# Main.net
KiCad netlist of a schematic drawn in Altium Designer
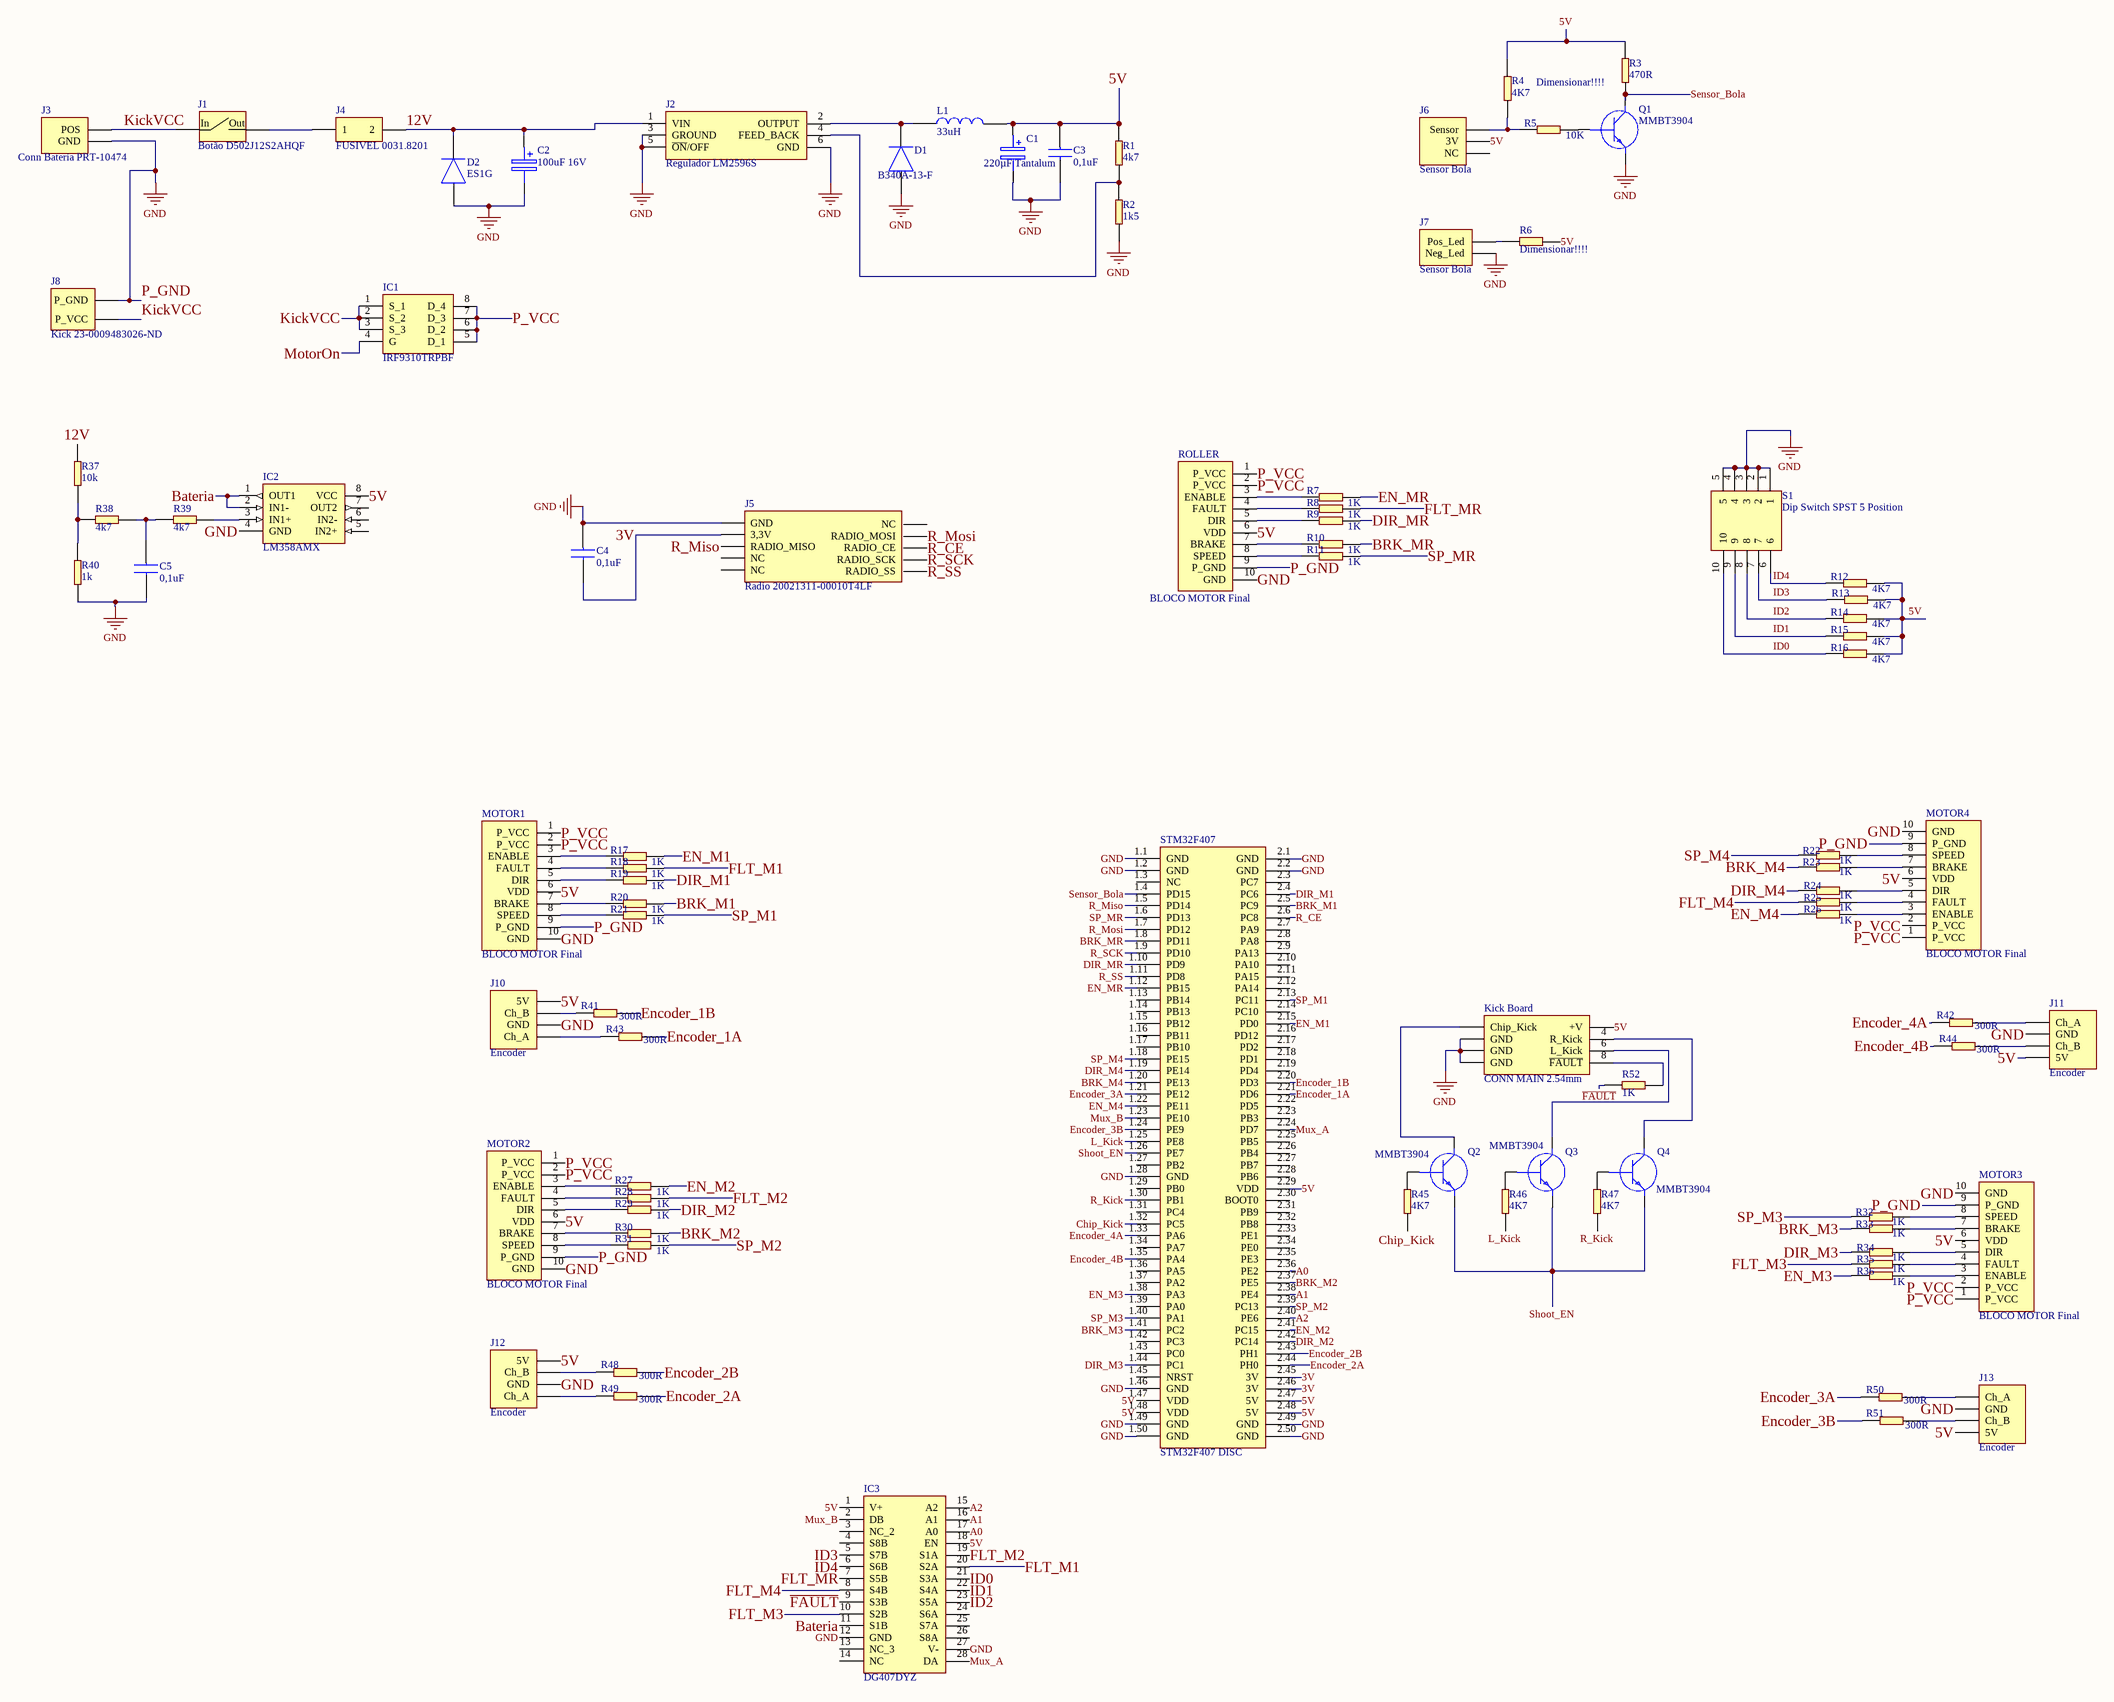
[diagram p0: Main.SchDoc]

(export (version "E")
  (design (tool "Eeschema 10.0.6"))
  (components
    (comp (ref "C1")
      (value "220µF Tantalum")
      (footprint "LIB_PCB_MAIN:CAP C2 SMD 6032 (2312)")
      (fields
        (field (name "MANUFACTURER_PART_NUMBER") "EEE-FK1E101P")
        (field (name "MOUSER PART NUMBER") "667-EEE-FK1E101P")
      )
      (libsource (lib "LIB_SCH_MAIN") (part "CAP C2 Tantalum"))
    )
    (comp (ref "C2")
      (value "100uF 16V")
      (footprint "LIB_PCB_MAIN:C1 CAP ALUM SMD")
      (fields
        (field (name "MANUFACTURER_PART_NUMBER") "EEE-1CA101WP")
        (field (name "MOUSER PART NUMBER") "667-EEE-1CA101WP")
        (field (name "RS PART NUMBER") "8077884")
      )
      (libsource (lib "LIB_SCH_MAIN") (part "C1 CAP ALUM 16V EEE-1CA101WP"))
    )
    (comp (ref "C3")
      (value "0,1uF")
      (footprint "LIB_PCB_MAIN:CAP C3 0603 SMD")
      (fields
        (field (name "MANUFACTURER_PART_NUMBER") "C3216C0G1H103J060AA")
        (field (name "MOUSER PART NUMBER") "810-C3216C0G1H103J-1")
        (field (name "RS PART NUMBER") "7407467P")
      )
      (libsource (lib "LIB_SCH_MAIN") (part "CAP C3 0603"))
    )
    (comp (ref "C4")
      (value "0,1uF")
      (footprint "LIB_PCB_MAIN:CAP C3 0603 SMD")
      (fields
        (field (name "MANUFACTURER_PART_NUMBER") "C3216C0G1H103J060AA")
        (field (name "MOUSER PART NUMBER") "810-C3216C0G1H103J-1")
        (field (name "RS PART NUMBER") "7407467P")
      )
      (libsource (lib "LIB_SCH_MAIN") (part "CAP C3 0603"))
    )
    (comp (ref "C5")
      (value "0,1uF")
      (footprint "LIB_PCB_MAIN:CAP C3 0603 SMD")
      (fields
        (field (name "MANUFACTURER_PART_NUMBER") "C3216C0G1H103J060AA")
        (field (name "MOUSER PART NUMBER") "810-C3216C0G1H103J-1")
        (field (name "RS PART NUMBER") "7407467P")
      )
      (libsource (lib "LIB_SCH_MAIN") (part "CAP C3 0603"))
    )
    (comp (ref "D1")
      (value "B340A-13-F")
      (footprint "LIB_PCB_MAIN:Diodo D1, D2")
      (description "Diode Schottky 40V 3A Surface Mount SMA\r\n\r\nB340A-FDITR-ND\r\n\r\nB340A-13-F")
      (fields (field (name "MANUFACTURER_PART_NUMBER") "ES1G"))
      (libsource (lib "LIB_SCH_MAIN") (part "Diodo D2 B340A-13-F"))
    )
    (comp (ref "D2")
      (value "ES1G")
      (footprint "LIB_PCB_MAIN:Diodo D1, D2")
      (description "Diode Standard 400V 1A Surface Mount SMA (DO-214AC)\r\n\r\nS1GFSCT-ND")
      (libsource (lib "LIB_SCH_MAIN") (part "Diodo D1 ES1G"))
    )
    (comp (ref "IC1")
      (value "IRF9310TRPBF")
      (footprint "LIB_PCB_MAIN:Mosfet P_VCC")
      (fields
        (field (name "MANUFACTURER_PART_NUMBER") "IRF9310PBF")
        (field (name "MOUSER PART NUMBER") "942-IRF9310PBF")
        (field (name "RS PART NUMBER") "7259234P")
      )
      (libsource (lib "LIB_SCH_MAIN") (part "Mosfet P_VCC"))
    )
    (comp (ref "IC2")
      (value "LM358AMX")
      (footprint "LIB_PCB_MAIN:OP AMP Bateria")
      (fields (field (name "MOUSER PART NUMBER") "512-LM358AMX") (field (name "RS PART NUMBER") "7599399P"))
      (libsource (lib "LIB_SCH_MAIN") (part "OP AMP Bateria"))
    )
    (comp (ref "IC3")
      (value "DG407DYZ")
      (footprint "LIB_PCB_MAIN:MUX 2x 8:1")
      (description "IC MULTIPLEXER DUAL 8X1 28SOIC\r\n\r\n2 Circuit IC Switch 8:1 100Ohm 28-SOIC\r\n\r\nDG407DYZ")
      (fields (field (name "MOUSER PART NUMBER") "968-DG407DYZ"))
      (libsource (lib "LIB_SCH_MAIN") (part "MUX 2x 8{colon}1"))
    )
    (comp (ref "J1")
      (value "Botão D502J12S2AHQF")
      (footprint "LIB_PCB_MAIN:Botão Bateria Main")
      (fields
        (field (name "MANUFACTURER_PART_NUMBER") "0031.8201")
        (field (name "MOUSER PART NUMBER") "693-0031.8201")
        (field (name "RS PART NUMBER") "2508764386")
      )
      (libsource (lib "LIB_SCH_MAIN") (part "Botão Bateria Main"))
    )
    (comp (ref "J2")
      (value "Regulador LM2596S")
      (footprint "LIB_PCB_MAIN:LM2596S50TR")
      (fields (field (name "MANUFACTURER_PART_NUMBER") "LM2596S-5.0/TR"))
      (libsource (lib "LIB_SCH_Main") (part "Regulador LM2596S 12V - 5V"))
    )
    (comp (ref "J3")
      (value "Conn Bateria PRT-10474")
      (footprint "LIB_PCB_MAIN:Conn Bateria Bolado")
      (description "XT60 CONNECTORS MALE\r\n\r\nPRT-10474\r\n\r\n1568-1816-ND")
      (fields
        (field (name "MANUFACTURER_PART_NUMBER") "PRT-10474")
        (field (name "MOUSER PART NUMBER") "474-PRT-10474")
      )
      (libsource (lib "LIB_SCH_MAIN") (part "Conn Bateria Bolado"))
    )
    (comp (ref "J4")
      (value "FUSIVEL 0031.8201")
      (footprint "LIB_PCB_MAIN:PORTA FUSIVEL")
      (description "Fuse Block 10A 500V 1 Circuit Cartridge Through Hole\r\n\r\n486-1258-ND\r\n\r\n0031.8201")
      (fields
        (field (name "MANUFACTURER_PART_NUMBER") "0031.8201")
        (field (name "MOUSER PART NUMBER") "693-0031.8201")
      )
      (libsource (lib "LIB_SCH_MAIN") (part "PORTA FUSIVEL 0031.8201"))
    )
    (comp (ref "J5")
      (value "Radio 20021311-00010T4LF")
      (footprint "LIB_PCB_MAIN:CONN Radio")
      (description "CONN RCPT 1.27mm 10POS 0.05 GOLD PCB\r\n\r\n20021311-00010T4LF\r\n\r\n609-3754-ND")
      (fields
        (field (name "MANUFACTURER_PART_NUMBER") "20021311-00010T4LF")
        (field (name "MOUSER PART NUMBER") "649-221311-00010T4LF")
      )
      (libsource (lib "LIB_SCH_Main") (part "CONN RADIO"))
    )
    (comp (ref "J6")
      (value "Sensor Bola")
      (footprint "LIB_PCB_MAIN:Conn Receptor Infra")
      (fields
        (field (name "MANUFACTURER_PART_NUMBER") "292161-3")
        (field (name "MOUSER PART NUMBER") "571-292161-3")
        (field (name "RS PART NUMBER") "6801610")
      )
      (libsource (lib "LIB_SCH_MAIN") (part "Conn Receptor Infra"))
    )
    (comp (ref "J7")
      (value "Sensor Bola")
      (footprint "LIB_PCB_MAIN:Conn Emisor Infra")
      (fields
        (field (name "MANUFACTURER_PART_NUMBER") "292161-3")
        (field (name "MOUSER PART NUMBER") "571-292161-3")
        (field (name "RS PART NUMBER") "6801610")
      )
      (libsource (lib "LIB_SCH_Main") (part "Conn Emissor Infra"))
    )
    (comp (ref "J8")
      (value "Kick 23-0009483026-ND")
      (footprint "LIB_PCB_MAIN:Battery Main to Kick Connector")
      (description "23-0009483026-ND")
      (fields
        (field (name "MANUFACTURER_PART_NUMBER") "22-05-3021")
        (field (name "MOUSER PART NUMBER") "538-22-05-3021")
      )
      (libsource (lib "LIB_SCH_Main") (part "Battery Main to Kick"))
    )
    (comp (ref "J10")
      (value "Encoder")
      (footprint "LIB_PCB_MAIN:Conn Encoder")
      (fields
        (field (name "MANUFACTURER_PART_NUMBER") "292161-3")
        (field (name "MOUSER PART NUMBER") "571-292161-3")
        (field (name "RS PART NUMBER") "6801610")
      )
      (libsource (lib "") (part "Conn Encoder_1"))
    )
    (comp (ref "J11")
      (value "Encoder")
      (footprint "LIB_PCB_MAIN:Conn Encoder")
      (fields
        (field (name "MANUFACTURER_PART_NUMBER") "292161-3")
        (field (name "MOUSER PART NUMBER") "571-292161-3")
        (field (name "RS PART NUMBER") "6801610")
      )
      (libsource (lib "LIB_SCH_Main") (part "Conn Encoder"))
    )
    (comp (ref "J12")
      (value "Encoder")
      (footprint "LIB_PCB_MAIN:Conn Encoder")
      (fields
        (field (name "MANUFACTURER_PART_NUMBER") "292161-3")
        (field (name "MOUSER PART NUMBER") "571-292161-3")
        (field (name "RS PART NUMBER") "6801610")
      )
      (libsource (lib "") (part "Conn Encoder_1"))
    )
    (comp (ref "J13")
      (value "Encoder")
      (footprint "LIB_PCB_MAIN:Conn Encoder")
      (fields
        (field (name "MANUFACTURER_PART_NUMBER") "292161-3")
        (field (name "MOUSER PART NUMBER") "571-292161-3")
        (field (name "RS PART NUMBER") "6801610")
      )
      (libsource (lib "LIB_SCH_Main") (part "Conn Encoder"))
    )
    (comp (ref "Kick Board")
      (value "CONN MAIN 2.54mm")
      (footprint "LIB_PCB_MAIN:Kick Board")
      (description "Connector\r\n\r\nCONN HEADER VERT 8POS 2.54MM\r\n\r\nM20-9980445\r\n\r\n952-2122-ND")
      (fields
        (field (name "MANUFACTURER_PART_NUMBER") "20021311-00010T4LF")
        (field (name "MOUSER PART NUMBER") "649-221311-00010T4LF")
      )
      (libsource (lib "LIB_SCH_MAIN") (part "Kick Board"))
    )
    (comp (ref "L1")
      (value "33uH")
      (footprint "LIB_PCB_MAIN:Indutor DR124-330-R")
      (fields
        (field (name "MANUFACTURER_PART_NUMBER") "DR124-221-R")
        (field (name "RS PART NUMBER") "7700915")
      )
      (libsource (lib "LIB_SCH_MAIN") (part "Indutor DR124-221-R"))
    )
    (comp (ref "MOTOR1")
      (value "BLOCO MOTOR Final")
      (footprint "LIB_PCB_MAIN:BlocoMotor Final")
      (libsource (lib "LIB_SCH_MAIN") (part "BLOCO MOTOR Final"))
    )
    (comp (ref "MOTOR2")
      (value "BLOCO MOTOR Final")
      (footprint "LIB_PCB_MAIN:BlocoMotor Final")
      (libsource (lib "LIB_SCH_MAIN") (part "BLOCO MOTOR Final"))
    )
    (comp (ref "MOTOR3")
      (value "BLOCO MOTOR Final")
      (footprint "LIB_PCB_MAIN:BlocoMotor Final")
      (libsource (lib "") (part "BLOCO MOTOR Final_1"))
    )
    (comp (ref "MOTOR4")
      (value "BLOCO MOTOR Final")
      (footprint "LIB_PCB_MAIN:BlocoMotor Final")
      (libsource (lib "") (part "BLOCO MOTOR Final_1"))
    )
    (comp (ref "Q1")
      (value "MMBT3904")
      (footprint "Mini Transistor")
      (fields (field (name "MOUSER PART NUMBER") "512-MMBT3904") (field (name "RS PART NUMBER") "7390303P"))
      (libsource (lib "LIB_SCH_MAIN") (part "Mini_Transistor"))
    )
    (comp (ref "Q2")
      (value "MMBT3904")
      (footprint "Mini Transistor")
      (fields (field (name "MOUSER PART NUMBER") "512-MMBT3904") (field (name "RS PART NUMBER") "7390303P"))
      (libsource (lib "LIB_SCH_MAIN") (part "Mini_Transistor"))
    )
    (comp (ref "Q3")
      (value "MMBT3904")
      (footprint "Mini Transistor")
      (fields (field (name "MOUSER PART NUMBER") "512-MMBT3904") (field (name "RS PART NUMBER") "7390303P"))
      (libsource (lib "LIB_SCH_MAIN") (part "Mini_Transistor"))
    )
    (comp (ref "Q4")
      (value "MMBT3904")
      (footprint "Mini Transistor")
      (fields (field (name "MOUSER PART NUMBER") "512-MMBT3904") (field (name "RS PART NUMBER") "7390303P"))
      (libsource (lib "LIB_SCH_MAIN") (part "Mini_Transistor"))
    )
    (comp (ref "R1")
      (value "4k7")
      (footprint "LIB_PCB_MAIN:RES 0805")
      (description "Resistor")
      (fields
        (field (name "MANUFACTURER_PART_NUMBER") "CPF0805B105RE1")
        (field (name "MOUSER PART NUMBER") "279-CPF0805B105RE1")
      )
      (libsource (lib "") (part "Resistor 0805_3"))
    )
    (comp (ref "R2")
      (value "1k5")
      (footprint "LIB_PCB_MAIN:RES 0805")
      (description "Resistor")
      (fields
        (field (name "MANUFACTURER_PART_NUMBER") "CPF0805B105RE1")
        (field (name "MOUSER PART NUMBER") "279-CPF0805B105RE1")
      )
      (libsource (lib "") (part "Resistor 0805_3"))
    )
    (comp (ref "R3")
      (value "470R")
      (footprint "LIB_PCB_MAIN:RES 0805")
      (description "Resistor")
      (fields
        (field (name "MANUFACTURER_PART_NUMBER") "CPF0805B105RE1")
        (field (name "MOUSER PART NUMBER") "279-CPF0805B105RE1")
      )
      (libsource (lib "") (part "Resistor 0805_1"))
    )
    (comp (ref "R4")
      (value "4K7")
      (footprint "LIB_PCB_MAIN:RES 0805")
      (description "Resistor")
      (fields
        (field (name "MANUFACTURER_PART_NUMBER") "CPF0805B105RE1")
        (field (name "MOUSER PART NUMBER") "279-CPF0805B105RE1")
      )
      (libsource (lib "") (part "Resistor 0805_1"))
    )
    (comp (ref "R5")
      (value "10K")
      (footprint "LIB_PCB_MAIN:RES 0805")
      (description "Resistor")
      (fields
        (field (name "MANUFACTURER_PART_NUMBER") "CPF0805B105RE1")
        (field (name "MOUSER PART NUMBER") "279-CPF0805B105RE1")
      )
      (libsource (lib "LIB_SCH_MAIN") (part "Resistor 0805"))
    )
    (comp (ref "R6")
      (value "Dimensionar!!!!")
      (footprint "LIB_PCB_MAIN:RES 0805")
      (description "Resistor")
      (fields
        (field (name "MANUFACTURER_PART_NUMBER") "CPF0805B105RE1")
        (field (name "MOUSER PART NUMBER") "279-CPF0805B105RE1")
      )
      (libsource (lib "") (part "Resistor 0805_2"))
    )
    (comp (ref "R7")
      (value "1K")
      (footprint "LIB_PCB_MAIN:RES 0805")
      (description "Resistor")
      (fields
        (field (name "MANUFACTURER_PART_NUMBER") "CPF0805B105RE1")
        (field (name "MOUSER PART NUMBER") "279-CPF0805B105RE1")
      )
      (libsource (lib "LIB_SCH_MAIN") (part "Resistor 0805"))
    )
    (comp (ref "R8")
      (value "1K")
      (footprint "LIB_PCB_MAIN:RES 0805")
      (description "Resistor")
      (fields
        (field (name "MANUFACTURER_PART_NUMBER") "CPF0805B105RE1")
        (field (name "MOUSER PART NUMBER") "279-CPF0805B105RE1")
      )
      (libsource (lib "LIB_SCH_MAIN") (part "Resistor 0805"))
    )
    (comp (ref "R9")
      (value "1K")
      (footprint "LIB_PCB_MAIN:RES 0805")
      (description "Resistor")
      (fields
        (field (name "MANUFACTURER_PART_NUMBER") "CPF0805B105RE1")
        (field (name "MOUSER PART NUMBER") "279-CPF0805B105RE1")
      )
      (libsource (lib "LIB_SCH_MAIN") (part "Resistor 0805"))
    )
    (comp (ref "R10")
      (value "1K")
      (footprint "LIB_PCB_MAIN:RES 0805")
      (description "Resistor")
      (fields
        (field (name "MANUFACTURER_PART_NUMBER") "CPF0805B105RE1")
        (field (name "MOUSER PART NUMBER") "279-CPF0805B105RE1")
      )
      (libsource (lib "LIB_SCH_MAIN") (part "Resistor 0805"))
    )
    (comp (ref "R11")
      (value "1K")
      (footprint "LIB_PCB_MAIN:RES 0805")
      (description "Resistor")
      (fields
        (field (name "MANUFACTURER_PART_NUMBER") "CPF0805B105RE1")
        (field (name "MOUSER PART NUMBER") "279-CPF0805B105RE1")
      )
      (libsource (lib "LIB_SCH_MAIN") (part "Resistor 0805"))
    )
    (comp (ref "R12")
      (value "4K7")
      (footprint "LIB_PCB_MAIN:RES 0805")
      (description "Resistor")
      (fields
        (field (name "MANUFACTURER_PART_NUMBER") "CPF0805B105RE1")
        (field (name "MOUSER PART NUMBER") "279-CPF0805B105RE1")
      )
      (libsource (lib "LIB_SCH_MAIN") (part "Resistor 0805"))
    )
    (comp (ref "R13")
      (value "4K7")
      (footprint "LIB_PCB_MAIN:RES 0805")
      (description "Resistor")
      (fields
        (field (name "MANUFACTURER_PART_NUMBER") "CPF0805B105RE1")
        (field (name "MOUSER PART NUMBER") "279-CPF0805B105RE1")
      )
      (libsource (lib "LIB_SCH_MAIN") (part "Resistor 0805"))
    )
    (comp (ref "R14")
      (value "4K7")
      (footprint "LIB_PCB_MAIN:RES 0805")
      (description "Resistor")
      (fields
        (field (name "MANUFACTURER_PART_NUMBER") "CPF0805B105RE1")
        (field (name "MOUSER PART NUMBER") "279-CPF0805B105RE1")
      )
      (libsource (lib "LIB_SCH_MAIN") (part "Resistor 0805"))
    )
    (comp (ref "R15")
      (value "4K7")
      (footprint "LIB_PCB_MAIN:RES 0805")
      (description "Resistor")
      (fields
        (field (name "MANUFACTURER_PART_NUMBER") "CPF0805B105RE1")
        (field (name "MOUSER PART NUMBER") "279-CPF0805B105RE1")
      )
      (libsource (lib "LIB_SCH_MAIN") (part "Resistor 0805"))
    )
    (comp (ref "R16")
      (value "4K7")
      (footprint "LIB_PCB_MAIN:RES 0805")
      (description "Resistor")
      (fields
        (field (name "MANUFACTURER_PART_NUMBER") "CPF0805B105RE1")
        (field (name "MOUSER PART NUMBER") "279-CPF0805B105RE1")
      )
      (libsource (lib "LIB_SCH_MAIN") (part "Resistor 0805"))
    )
    (comp (ref "R17")
      (value "1K")
      (footprint "LIB_PCB_MAIN:RES 0805")
      (description "Resistor")
      (fields
        (field (name "MANUFACTURER_PART_NUMBER") "CPF0805B105RE1")
        (field (name "MOUSER PART NUMBER") "279-CPF0805B105RE1")
      )
      (libsource (lib "LIB_SCH_MAIN") (part "Resistor 0805"))
    )
    (comp (ref "R18")
      (value "1K")
      (footprint "LIB_PCB_MAIN:RES 0805")
      (description "Resistor")
      (fields
        (field (name "MANUFACTURER_PART_NUMBER") "CPF0805B105RE1")
        (field (name "MOUSER PART NUMBER") "279-CPF0805B105RE1")
      )
      (libsource (lib "LIB_SCH_MAIN") (part "Resistor 0805"))
    )
    (comp (ref "R19")
      (value "1K")
      (footprint "LIB_PCB_MAIN:RES 0805")
      (description "Resistor")
      (fields
        (field (name "MANUFACTURER_PART_NUMBER") "CPF0805B105RE1")
        (field (name "MOUSER PART NUMBER") "279-CPF0805B105RE1")
      )
      (libsource (lib "LIB_SCH_MAIN") (part "Resistor 0805"))
    )
    (comp (ref "R20")
      (value "1K")
      (footprint "LIB_PCB_MAIN:RES 0805")
      (description "Resistor")
      (fields
        (field (name "MANUFACTURER_PART_NUMBER") "CPF0805B105RE1")
        (field (name "MOUSER PART NUMBER") "279-CPF0805B105RE1")
      )
      (libsource (lib "LIB_SCH_MAIN") (part "Resistor 0805"))
    )
    (comp (ref "R21")
      (value "1K")
      (footprint "LIB_PCB_MAIN:RES 0805")
      (description "Resistor")
      (fields
        (field (name "MANUFACTURER_PART_NUMBER") "CPF0805B105RE1")
        (field (name "MOUSER PART NUMBER") "279-CPF0805B105RE1")
      )
      (libsource (lib "LIB_SCH_MAIN") (part "Resistor 0805"))
    )
    (comp (ref "R22")
      (value "1K")
      (footprint "LIB_PCB_MAIN:RES 0805")
      (description "Resistor")
      (fields
        (field (name "MANUFACTURER_PART_NUMBER") "CPF0805B105RE1")
        (field (name "MOUSER PART NUMBER") "279-CPF0805B105RE1")
      )
      (libsource (lib "") (part "Resistor 0805_2"))
    )
    (comp (ref "R23")
      (value "1K")
      (footprint "LIB_PCB_MAIN:RES 0805")
      (description "Resistor")
      (fields
        (field (name "MANUFACTURER_PART_NUMBER") "CPF0805B105RE1")
        (field (name "MOUSER PART NUMBER") "279-CPF0805B105RE1")
      )
      (libsource (lib "") (part "Resistor 0805_2"))
    )
    (comp (ref "R24")
      (value "1K")
      (footprint "LIB_PCB_MAIN:RES 0805")
      (description "Resistor")
      (fields
        (field (name "MANUFACTURER_PART_NUMBER") "CPF0805B105RE1")
        (field (name "MOUSER PART NUMBER") "279-CPF0805B105RE1")
      )
      (libsource (lib "") (part "Resistor 0805_2"))
    )
    (comp (ref "R25")
      (value "1K")
      (footprint "LIB_PCB_MAIN:RES 0805")
      (description "Resistor")
      (fields
        (field (name "MANUFACTURER_PART_NUMBER") "CPF0805B105RE1")
        (field (name "MOUSER PART NUMBER") "279-CPF0805B105RE1")
      )
      (libsource (lib "") (part "Resistor 0805_2"))
    )
    (comp (ref "R26")
      (value "1K")
      (footprint "LIB_PCB_MAIN:RES 0805")
      (description "Resistor")
      (fields
        (field (name "MANUFACTURER_PART_NUMBER") "CPF0805B105RE1")
        (field (name "MOUSER PART NUMBER") "279-CPF0805B105RE1")
      )
      (libsource (lib "") (part "Resistor 0805_2"))
    )
    (comp (ref "R27")
      (value "1K")
      (footprint "LIB_PCB_MAIN:RES 0805")
      (description "Resistor")
      (fields
        (field (name "MANUFACTURER_PART_NUMBER") "CPF0805B105RE1")
        (field (name "MOUSER PART NUMBER") "279-CPF0805B105RE1")
      )
      (libsource (lib "LIB_SCH_MAIN") (part "Resistor 0805"))
    )
    (comp (ref "R28")
      (value "1K")
      (footprint "LIB_PCB_MAIN:RES 0805")
      (description "Resistor")
      (fields
        (field (name "MANUFACTURER_PART_NUMBER") "CPF0805B105RE1")
        (field (name "MOUSER PART NUMBER") "279-CPF0805B105RE1")
      )
      (libsource (lib "LIB_SCH_MAIN") (part "Resistor 0805"))
    )
    (comp (ref "R29")
      (value "1K")
      (footprint "LIB_PCB_MAIN:RES 0805")
      (description "Resistor")
      (fields
        (field (name "MANUFACTURER_PART_NUMBER") "CPF0805B105RE1")
        (field (name "MOUSER PART NUMBER") "279-CPF0805B105RE1")
      )
      (libsource (lib "LIB_SCH_MAIN") (part "Resistor 0805"))
    )
    (comp (ref "R30")
      (value "1K")
      (footprint "LIB_PCB_MAIN:RES 0805")
      (description "Resistor")
      (fields
        (field (name "MANUFACTURER_PART_NUMBER") "CPF0805B105RE1")
        (field (name "MOUSER PART NUMBER") "279-CPF0805B105RE1")
      )
      (libsource (lib "LIB_SCH_MAIN") (part "Resistor 0805"))
    )
    (comp (ref "R31")
      (value "1K")
      (footprint "LIB_PCB_MAIN:RES 0805")
      (description "Resistor")
      (fields
        (field (name "MANUFACTURER_PART_NUMBER") "CPF0805B105RE1")
        (field (name "MOUSER PART NUMBER") "279-CPF0805B105RE1")
      )
      (libsource (lib "LIB_SCH_MAIN") (part "Resistor 0805"))
    )
    (comp (ref "R32")
      (value "1K")
      (footprint "LIB_PCB_MAIN:RES 0805")
      (description "Resistor")
      (fields
        (field (name "MANUFACTURER_PART_NUMBER") "CPF0805B105RE1")
        (field (name "MOUSER PART NUMBER") "279-CPF0805B105RE1")
      )
      (libsource (lib "") (part "Resistor 0805_2"))
    )
    (comp (ref "R33")
      (value "1K")
      (footprint "LIB_PCB_MAIN:RES 0805")
      (description "Resistor")
      (fields
        (field (name "MANUFACTURER_PART_NUMBER") "CPF0805B105RE1")
        (field (name "MOUSER PART NUMBER") "279-CPF0805B105RE1")
      )
      (libsource (lib "") (part "Resistor 0805_2"))
    )
    (comp (ref "R34")
      (value "1K")
      (footprint "LIB_PCB_MAIN:RES 0805")
      (description "Resistor")
      (fields
        (field (name "MANUFACTURER_PART_NUMBER") "CPF0805B105RE1")
        (field (name "MOUSER PART NUMBER") "279-CPF0805B105RE1")
      )
      (libsource (lib "") (part "Resistor 0805_2"))
    )
    (comp (ref "R35")
      (value "1K")
      (footprint "LIB_PCB_MAIN:RES 0805")
      (description "Resistor")
      (fields
        (field (name "MANUFACTURER_PART_NUMBER") "CPF0805B105RE1")
        (field (name "MOUSER PART NUMBER") "279-CPF0805B105RE1")
      )
      (libsource (lib "") (part "Resistor 0805_2"))
    )
    (comp (ref "R36")
      (value "1K")
      (footprint "LIB_PCB_MAIN:RES 0805")
      (description "Resistor")
      (fields
        (field (name "MANUFACTURER_PART_NUMBER") "CPF0805B105RE1")
        (field (name "MOUSER PART NUMBER") "279-CPF0805B105RE1")
      )
      (libsource (lib "") (part "Resistor 0805_2"))
    )
    (comp (ref "R37")
      (value "10k")
      (footprint "LIB_PCB_MAIN:RES 0805")
      (description "Resistor")
      (fields
        (field (name "MANUFACTURER_PART_NUMBER") "CPF0805B105RE1")
        (field (name "MOUSER PART NUMBER") "279-CPF0805B105RE1")
      )
      (libsource (lib "") (part "Resistor 0805_3"))
    )
    (comp (ref "R38")
      (value "4k7")
      (footprint "LIB_PCB_MAIN:RES 0805")
      (description "Resistor")
      (fields
        (field (name "MANUFACTURER_PART_NUMBER") "CPF0805B105RE1")
        (field (name "MOUSER PART NUMBER") "279-CPF0805B105RE1")
      )
      (libsource (lib "LIB_SCH_MAIN") (part "Resistor 0805"))
    )
    (comp (ref "R39")
      (value "4k7")
      (footprint "LIB_PCB_MAIN:RES 0805")
      (description "Resistor")
      (fields
        (field (name "MANUFACTURER_PART_NUMBER") "CPF0805B105RE1")
        (field (name "MOUSER PART NUMBER") "279-CPF0805B105RE1")
      )
      (libsource (lib "LIB_SCH_MAIN") (part "Resistor 0805"))
    )
    (comp (ref "R40")
      (value "1k")
      (footprint "LIB_PCB_MAIN:RES 0805")
      (description "Resistor")
      (fields
        (field (name "MANUFACTURER_PART_NUMBER") "CPF0805B105RE1")
        (field (name "MOUSER PART NUMBER") "279-CPF0805B105RE1")
      )
      (libsource (lib "") (part "Resistor 0805_3"))
    )
    (comp (ref "R41")
      (value "300R")
      (footprint "LIB_PCB_MAIN:RES 0805")
      (description "Resistor")
      (fields
        (field (name "MANUFACTURER_PART_NUMBER") "CPF0805B105RE1")
        (field (name "MOUSER PART NUMBER") "279-CPF0805B105RE1")
      )
      (libsource (lib "LIB_SCH_MAIN") (part "Resistor 0805"))
    )
    (comp (ref "R42")
      (value "300R")
      (footprint "LIB_PCB_MAIN:RES 0805")
      (description "Resistor")
      (fields
        (field (name "MANUFACTURER_PART_NUMBER") "CPF0805B105RE1")
        (field (name "MOUSER PART NUMBER") "279-CPF0805B105RE1")
      )
      (libsource (lib "LIB_SCH_MAIN") (part "Resistor 0805"))
    )
    (comp (ref "R43")
      (value "300R")
      (footprint "LIB_PCB_MAIN:RES 0805")
      (description "Resistor")
      (fields
        (field (name "MANUFACTURER_PART_NUMBER") "CPF0805B105RE1")
        (field (name "MOUSER PART NUMBER") "279-CPF0805B105RE1")
      )
      (libsource (lib "LIB_SCH_MAIN") (part "Resistor 0805"))
    )
    (comp (ref "R44")
      (value "300R")
      (footprint "LIB_PCB_MAIN:RES 0805")
      (description "Resistor")
      (fields
        (field (name "MANUFACTURER_PART_NUMBER") "CPF0805B105RE1")
        (field (name "MOUSER PART NUMBER") "279-CPF0805B105RE1")
      )
      (libsource (lib "LIB_SCH_MAIN") (part "Resistor 0805"))
    )
    (comp (ref "R45")
      (value "4K7")
      (footprint "LIB_PCB_MAIN:RES 0805")
      (description "Resistor")
      (fields
        (field (name "MANUFACTURER_PART_NUMBER") "CPF0805B105RE1")
        (field (name "MOUSER PART NUMBER") "279-CPF0805B105RE1")
      )
      (libsource (lib "") (part "Resistor 0805_1"))
    )
    (comp (ref "R46")
      (value "4K7")
      (footprint "LIB_PCB_MAIN:RES 0805")
      (description "Resistor")
      (fields
        (field (name "MANUFACTURER_PART_NUMBER") "CPF0805B105RE1")
        (field (name "MOUSER PART NUMBER") "279-CPF0805B105RE1")
      )
      (libsource (lib "") (part "Resistor 0805_1"))
    )
    (comp (ref "R47")
      (value "4K7")
      (footprint "LIB_PCB_MAIN:RES 0805")
      (description "Resistor")
      (fields
        (field (name "MANUFACTURER_PART_NUMBER") "CPF0805B105RE1")
        (field (name "MOUSER PART NUMBER") "279-CPF0805B105RE1")
      )
      (libsource (lib "") (part "Resistor 0805_1"))
    )
    (comp (ref "R48")
      (value "300R")
      (footprint "LIB_PCB_MAIN:RES 0805")
      (description "Resistor")
      (fields
        (field (name "MANUFACTURER_PART_NUMBER") "CPF0805B105RE1")
        (field (name "MOUSER PART NUMBER") "279-CPF0805B105RE1")
      )
      (libsource (lib "LIB_SCH_MAIN") (part "Resistor 0805"))
    )
    (comp (ref "R49")
      (value "300R")
      (footprint "LIB_PCB_MAIN:RES 0805")
      (description "Resistor")
      (fields
        (field (name "MANUFACTURER_PART_NUMBER") "CPF0805B105RE1")
        (field (name "MOUSER PART NUMBER") "279-CPF0805B105RE1")
      )
      (libsource (lib "LIB_SCH_MAIN") (part "Resistor 0805"))
    )
    (comp (ref "R50")
      (value "300R")
      (footprint "LIB_PCB_MAIN:RES 0805")
      (description "Resistor")
      (fields
        (field (name "MANUFACTURER_PART_NUMBER") "CPF0805B105RE1")
        (field (name "MOUSER PART NUMBER") "279-CPF0805B105RE1")
      )
      (libsource (lib "LIB_SCH_MAIN") (part "Resistor 0805"))
    )
    (comp (ref "R51")
      (value "300R")
      (footprint "LIB_PCB_MAIN:RES 0805")
      (description "Resistor")
      (fields
        (field (name "MANUFACTURER_PART_NUMBER") "CPF0805B105RE1")
        (field (name "MOUSER PART NUMBER") "279-CPF0805B105RE1")
      )
      (libsource (lib "LIB_SCH_MAIN") (part "Resistor 0805"))
    )
    (comp (ref "R52")
      (value "1K")
      (footprint "LIB_PCB_MAIN:RES 0805")
      (description "Resistor")
      (fields
        (field (name "MANUFACTURER_PART_NUMBER") "CPF0805B105RE1")
        (field (name "MOUSER PART NUMBER") "279-CPF0805B105RE1")
      )
      (libsource (lib "LIB_SCH_MAIN") (part "Resistor 0805"))
    )
    (comp (ref "ROLLER")
      (value "BLOCO MOTOR Final")
      (footprint "LIB_PCB_MAIN:BlocoMotor Final")
      (libsource (lib "LIB_SCH_MAIN") (part "BLOCO MOTOR Final"))
    )
    (comp (ref "S1")
      (value "Dip Switch SPST 5 Position")
      (footprint "LIB_PCB_MAIN:Dip Switch SPST 5 Position")
      (fields
        (field (name "MANUFACTURER_PART_NUMBER") "1825002-9")
        (field (name "RS PART NUMBER") "7182102P")
      )
      (libsource (lib "LIB_SCH_MAIN") (part "Dip Switch SPST 5 Position"))
    )
    (comp (ref "STM32F407")
      (value "STM32F407 DISC")
      (footprint "LIB_PCB_Main:STM32F407 DISC")
      (libsource (lib "LIB_SCH_Main") (part "STM32F407 DISC"))
    )
  )
  (nets
    (net (code "1") (name "/3V") (class "Default")
      (node (ref "C4") (pin "2") (pinfunction "2_2") (pintype "passive"))
      (node (ref "J5") (pin "2") (pinfunction "3,3V_2") (pintype "passive"))
      (node (ref "STM32F407") (pin "2.45") (pinfunction "3V_2.45") (pintype "passive"))
      (node (ref "STM32F407") (pin "2.46") (pinfunction "3V_2.46") (pintype "passive"))
    )
    (net (code "2") (name "/5V") (class "Default")
      (node (ref "C1") (pin "1") (pinfunction "+_1") (pintype "passive"))
      (node (ref "C3") (pin "1") (pinfunction "1_1") (pintype "passive"))
      (node (ref "IC2") (pin "8") (pinfunction "VCC_8") (pintype "power_in"))
      (node (ref "IC3") (pin "1") (pinfunction "V+_1") (pintype "passive"))
      (node (ref "IC3") (pin "18") (pinfunction "EN_18") (pintype "passive"))
      (node (ref "J10") (pin "4") (pinfunction "5V_4") (pintype "passive"))
      (node (ref "J11") (pin "4") (pinfunction "5V_4") (pintype "passive"))
      (node (ref "J12") (pin "4") (pinfunction "5V_4") (pintype "passive"))
      (node (ref "J13") (pin "4") (pinfunction "5V_4") (pintype "passive"))
      (node (ref "J6") (pin "2") (pinfunction "3V_2") (pintype "passive"))
      (node (ref "Kick Board") (pin "2") (pinfunction "+V_2") (pintype "passive"))
      (node (ref "L1") (pin "2") (pinfunction "2_2") (pintype "passive"))
      (node (ref "MOTOR1") (pin "6") (pinfunction "VDD_6") (pintype "passive"))
      (node (ref "MOTOR2") (pin "6") (pinfunction "VDD_6") (pintype "passive"))
      (node (ref "MOTOR3") (pin "6") (pinfunction "VDD_6") (pintype "passive"))
      (node (ref "MOTOR4") (pin "6") (pinfunction "VDD_6") (pintype "passive"))
      (node (ref "R1") (pin "2") (pinfunction "2_2") (pintype "passive"))
      (node (ref "R12") (pin "1") (pinfunction "1_1") (pintype "passive"))
      (node (ref "R13") (pin "1") (pinfunction "1_1") (pintype "passive"))
      (node (ref "R14") (pin "1") (pinfunction "1_1") (pintype "passive"))
      (node (ref "R15") (pin "1") (pinfunction "1_1") (pintype "passive"))
      (node (ref "R16") (pin "1") (pinfunction "1_1") (pintype "passive"))
      (node (ref "R3") (pin "1") (pinfunction "1_1") (pintype "passive"))
      (node (ref "R4") (pin "1") (pinfunction "1_1") (pintype "passive"))
      (node (ref "R6") (pin "2") (pinfunction "2_2") (pintype "passive"))
      (node (ref "ROLLER") (pin "6") (pinfunction "VDD_6") (pintype "passive"))
      (node (ref "STM32F407") (pin "1.47") (pinfunction "VDD_1.47") (pintype "passive"))
      (node (ref "STM32F407") (pin "1.48") (pinfunction "VDD_1.48") (pintype "passive"))
      (node (ref "STM32F407") (pin "2.29") (pinfunction "VDD_2.29") (pintype "passive"))
      (node (ref "STM32F407") (pin "2.47") (pinfunction "5V_2.47") (pintype "passive"))
      (node (ref "STM32F407") (pin "2.48") (pinfunction "5V_2.48") (pintype "passive"))
    )
    (net (code "3") (name "/12V") (class "Default")
      (node (ref "C2") (pin "1") (pinfunction "+_1") (pintype "passive"))
      (node (ref "D2") (pin "1") (pinfunction "K_1") (pintype "passive"))
      (node (ref "J2") (pin "1") (pinfunction "VIN_1") (pintype "passive"))
      (node (ref "J4") (pin "2") (pinfunction "2_2") (pintype "passive"))
      (node (ref "R37") (pin "2") (pinfunction "2_2") (pintype "passive"))
    )
    (net (code "4") (name "/A0") (class "Default")
      (node (ref "IC3") (pin "17") (pinfunction "A0_17") (pintype "passive"))
      (node (ref "STM32F407") (pin "2.36") (pinfunction "PE2_2.36") (pintype "passive"))
    )
    (net (code "5") (name "/A1") (class "Default")
      (node (ref "IC3") (pin "16") (pinfunction "A1_16") (pintype "passive"))
      (node (ref "STM32F407") (pin "2.38") (pinfunction "PE4_2.38") (pintype "passive"))
    )
    (net (code "6") (name "/A2") (class "Default")
      (node (ref "IC3") (pin "15") (pinfunction "A2_15") (pintype "passive"))
      (node (ref "STM32F407") (pin "2.40") (pinfunction "PE6_2.40") (pintype "passive"))
    )
    (net (code "7") (name "/BRK_M1") (class "Default")
      (node (ref "R20") (pin "1") (pinfunction "1_1") (pintype "passive"))
      (node (ref "STM32F407") (pin "2.5") (pinfunction "PC9_2.5") (pintype "passive"))
    )
    (net (code "8") (name "/BRK_M2") (class "Default")
      (node (ref "R30") (pin "1") (pinfunction "1_1") (pintype "passive"))
      (node (ref "STM32F407") (pin "2.37") (pinfunction "PE5_2.37") (pintype "passive"))
    )
    (net (code "9") (name "/BRK_M3") (class "Default")
      (node (ref "R33") (pin "1") (pinfunction "1_1") (pintype "passive"))
      (node (ref "STM32F407") (pin "1.41") (pinfunction "PC2_1.41") (pintype "passive"))
    )
    (net (code "10") (name "/BRK_M4") (class "Default")
      (node (ref "R23") (pin "1") (pinfunction "1_1") (pintype "passive"))
      (node (ref "STM32F407") (pin "1.20") (pinfunction "PE13_1.20") (pintype "passive"))
    )
    (net (code "11") (name "/BRK_MR") (class "Default")
      (node (ref "R10") (pin "1") (pinfunction "1_1") (pintype "passive"))
      (node (ref "STM32F407") (pin "1.8") (pinfunction "PD11_1.8") (pintype "passive"))
    )
    (net (code "12") (name "/Bateria") (class "Default")
      (node (ref "IC2") (pin "1") (pinfunction "OUT1_1") (pintype "output"))
      (node (ref "IC2") (pin "2") (pinfunction "IN1-_2") (pintype "input"))
      (node (ref "IC3") (pin "11") (pinfunction "S1B_11") (pintype "passive"))
    )
    (net (code "13") (name "/Chip_Kick") (class "Default")
      (node (ref "R45") (pin "2") (pinfunction "2_2") (pintype "passive"))
      (node (ref "STM32F407") (pin "1.32") (pinfunction "PC5_1.32") (pintype "passive"))
    )
    (net (code "14") (name "/DIR_M1") (class "Default")
      (node (ref "R19") (pin "1") (pinfunction "1_1") (pintype "passive"))
      (node (ref "STM32F407") (pin "2.4") (pinfunction "PC6_2.4") (pintype "passive"))
    )
    (net (code "15") (name "/DIR_M2") (class "Default")
      (node (ref "R29") (pin "1") (pinfunction "1_1") (pintype "passive"))
      (node (ref "STM32F407") (pin "2.42") (pinfunction "PC14_2.42") (pintype "passive"))
    )
    (net (code "16") (name "/DIR_M3") (class "Default")
      (node (ref "R34") (pin "1") (pinfunction "1_1") (pintype "passive"))
      (node (ref "STM32F407") (pin "1.44") (pinfunction "PC1_1.44") (pintype "passive"))
    )
    (net (code "17") (name "/DIR_M4") (class "Default")
      (node (ref "R24") (pin "1") (pinfunction "1_1") (pintype "passive"))
      (node (ref "STM32F407") (pin "1.19") (pinfunction "PE14_1.19") (pintype "passive"))
    )
    (net (code "18") (name "/DIR_MR") (class "Default")
      (node (ref "R9") (pin "1") (pinfunction "1_1") (pintype "passive"))
      (node (ref "STM32F407") (pin "1.10") (pinfunction "PD9_1.10") (pintype "passive"))
    )
    (net (code "19") (name "/EN_M1") (class "Default")
      (node (ref "R17") (pin "1") (pinfunction "1_1") (pintype "passive"))
      (node (ref "STM32F407") (pin "2.15") (pinfunction "PD0_2.15") (pintype "passive"))
    )
    (net (code "20") (name "/EN_M2") (class "Default")
      (node (ref "R27") (pin "1") (pinfunction "1_1") (pintype "passive"))
      (node (ref "STM32F407") (pin "2.41") (pinfunction "PC15_2.41") (pintype "passive"))
    )
    (net (code "21") (name "/EN_M3") (class "Default")
      (node (ref "R36") (pin "1") (pinfunction "1_1") (pintype "passive"))
      (node (ref "STM32F407") (pin "1.38") (pinfunction "PA3_1.38") (pintype "passive"))
    )
    (net (code "22") (name "/EN_M4") (class "Default")
      (node (ref "R26") (pin "1") (pinfunction "1_1") (pintype "passive"))
      (node (ref "STM32F407") (pin "1.22") (pinfunction "PE11_1.22") (pintype "passive"))
    )
    (net (code "23") (name "/EN_MR") (class "Default")
      (node (ref "R7") (pin "1") (pinfunction "1_1") (pintype "passive"))
      (node (ref "STM32F407") (pin "1.12") (pinfunction "PB15_1.12") (pintype "passive"))
    )
    (net (code "24") (name "/Encoder_1A") (class "Default")
      (node (ref "R43") (pin "1") (pinfunction "1_1") (pintype "passive"))
      (node (ref "STM32F407") (pin "2.21") (pinfunction "PD6_2.21") (pintype "passive"))
    )
    (net (code "25") (name "/Encoder_1B") (class "Default")
      (node (ref "R41") (pin "1") (pinfunction "1_1") (pintype "passive"))
      (node (ref "STM32F407") (pin "2.20") (pinfunction "PD3_2.20") (pintype "passive"))
    )
    (net (code "26") (name "/Encoder_2A") (class "Default")
      (node (ref "R49") (pin "1") (pinfunction "1_1") (pintype "passive"))
      (node (ref "STM32F407") (pin "2.44") (pinfunction "PH0_2.44") (pintype "passive"))
    )
    (net (code "27") (name "/Encoder_2B") (class "Default")
      (node (ref "R48") (pin "1") (pinfunction "1_1") (pintype "passive"))
      (node (ref "STM32F407") (pin "2.43") (pinfunction "PH1_2.43") (pintype "passive"))
    )
    (net (code "28") (name "/Encoder_3A") (class "Default")
      (node (ref "R50") (pin "2") (pinfunction "2_2") (pintype "passive"))
      (node (ref "STM32F407") (pin "1.21") (pinfunction "PE12_1.21") (pintype "passive"))
    )
    (net (code "29") (name "/Encoder_3B") (class "Default")
      (node (ref "R51") (pin "2") (pinfunction "2_2") (pintype "passive"))
      (node (ref "STM32F407") (pin "1.24") (pinfunction "PE9_1.24") (pintype "passive"))
    )
    (net (code "30") (name "/Encoder_4A") (class "Default")
      (node (ref "R42") (pin "2") (pinfunction "2_2") (pintype "passive"))
      (node (ref "STM32F407") (pin "1.33") (pinfunction "PA6_1.33") (pintype "passive"))
    )
    (net (code "31") (name "/Encoder_4B") (class "Default")
      (node (ref "R44") (pin "2") (pinfunction "2_2") (pintype "passive"))
      (node (ref "STM32F407") (pin "1.35") (pinfunction "PA4_1.35") (pintype "passive"))
    )
    (net (code "32") (name "/FLT_M1") (class "Default")
      (node (ref "IC3") (pin "20") (pinfunction "S2A_20") (pintype "passive"))
      (node (ref "R18") (pin "1") (pinfunction "1_1") (pintype "passive"))
    )
    (net (code "33") (name "/FLT_M2") (class "Default")
      (node (ref "IC3") (pin "19") (pinfunction "S1A_19") (pintype "passive"))
      (node (ref "R28") (pin "1") (pinfunction "1_1") (pintype "passive"))
    )
    (net (code "34") (name "/FLT_M3") (class "Default")
      (node (ref "IC3") (pin "10") (pinfunction "S2B_10") (pintype "passive"))
      (node (ref "R35") (pin "1") (pinfunction "1_1") (pintype "passive"))
    )
    (net (code "35") (name "/FLT_M4") (class "Default")
      (node (ref "IC3") (pin "8") (pinfunction "S4B_8") (pintype "passive"))
      (node (ref "R25") (pin "1") (pinfunction "1_1") (pintype "passive"))
    )
    (net (code "36") (name "/FLT_MR") (class "Default")
      (node (ref "IC3") (pin "7") (pinfunction "S5B_7") (pintype "passive"))
      (node (ref "R8") (pin "1") (pinfunction "1_1") (pintype "passive"))
    )
    (net (code "37") (name "/ID0") (class "Default")
      (node (ref "IC3") (pin "21") (pinfunction "S3A_21") (pintype "passive"))
      (node (ref "R16") (pin "2") (pinfunction "2_2") (pintype "passive"))
      (node (ref "S1") (pin "10") (pinfunction "10_10") (pintype "passive"))
    )
    (net (code "38") (name "/ID1") (class "Default")
      (node (ref "IC3") (pin "22") (pinfunction "S4A_22") (pintype "passive"))
      (node (ref "R15") (pin "2") (pinfunction "2_2") (pintype "passive"))
      (node (ref "S1") (pin "9") (pinfunction "9_9") (pintype "passive"))
    )
    (net (code "39") (name "/ID2") (class "Default")
      (node (ref "IC3") (pin "23") (pinfunction "S5A_23") (pintype "passive"))
      (node (ref "R14") (pin "2") (pinfunction "2_2") (pintype "passive"))
      (node (ref "S1") (pin "8") (pinfunction "8_8") (pintype "passive"))
    )
    (net (code "40") (name "/ID3") (class "Default")
      (node (ref "IC3") (pin "5") (pinfunction "S7B_5") (pintype "passive"))
      (node (ref "R13") (pin "2") (pinfunction "2_2") (pintype "passive"))
      (node (ref "S1") (pin "7") (pinfunction "7_7") (pintype "passive"))
    )
    (net (code "41") (name "/ID4") (class "Default")
      (node (ref "IC3") (pin "6") (pinfunction "S6B_6") (pintype "passive"))
      (node (ref "R12") (pin "2") (pinfunction "2_2") (pintype "passive"))
      (node (ref "S1") (pin "6") (pinfunction "6_6") (pintype "passive"))
    )
    (net (code "42") (name "/KickVCC") (class "Default")
      (node (ref "IC1") (pin "1") (pinfunction "S_1_1") (pintype "passive"))
      (node (ref "IC1") (pin "2") (pinfunction "S_2_2") (pintype "passive"))
      (node (ref "IC1") (pin "3") (pinfunction "S_3_3") (pintype "passive"))
      (node (ref "J1") (pin "1") (pinfunction "In_1") (pintype "passive"))
      (node (ref "J3") (pin "2") (pinfunction "POS_2") (pintype "power_in"))
      (node (ref "J8") (pin "2") (pinfunction "P_VCC_2") (pintype "passive"))
    )
    (net (code "43") (name "/L_Kick") (class "Default")
      (node (ref "R46") (pin "2") (pinfunction "2_2") (pintype "passive"))
      (node (ref "STM32F407") (pin "1.25") (pinfunction "PE8_1.25") (pintype "passive"))
    )
    (net (code "44") (name "/MotorOn") (class "Default")
      (node (ref "IC1") (pin "4") (pinfunction "G_4") (pintype "passive"))
    )
    (net (code "45") (name "/Mux_A") (class "Default")
      (node (ref "IC3") (pin "28") (pinfunction "DA_28") (pintype "passive"))
      (node (ref "STM32F407") (pin "2.24") (pinfunction "PD7_2.24") (pintype "passive"))
    )
    (net (code "46") (name "/Mux_B") (class "Default")
      (node (ref "IC3") (pin "2") (pinfunction "DB_2") (pintype "passive"))
      (node (ref "STM32F407") (pin "1.23") (pinfunction "PE10_1.23") (pintype "passive"))
    )
    (net (code "47") (name "/P_VCC") (class "Default")
      (node (ref "IC1") (pin "5") (pinfunction "D_1_5") (pintype "passive"))
      (node (ref "IC1") (pin "6") (pinfunction "D_2_6") (pintype "passive"))
      (node (ref "IC1") (pin "7") (pinfunction "D_3_7") (pintype "passive"))
      (node (ref "IC1") (pin "8") (pinfunction "D_4_8") (pintype "passive"))
      (node (ref "MOTOR1") (pin "1") (pinfunction "P_VCC_1") (pintype "passive"))
      (node (ref "MOTOR1") (pin "2") (pinfunction "P_VCC_2") (pintype "passive"))
      (node (ref "MOTOR2") (pin "1") (pinfunction "P_VCC_1") (pintype "passive"))
      (node (ref "MOTOR2") (pin "2") (pinfunction "P_VCC_2") (pintype "passive"))
      (node (ref "MOTOR3") (pin "1") (pinfunction "P_VCC_1") (pintype "passive"))
      (node (ref "MOTOR3") (pin "2") (pinfunction "P_VCC_2") (pintype "passive"))
      (node (ref "MOTOR4") (pin "1") (pinfunction "P_VCC_1") (pintype "passive"))
      (node (ref "MOTOR4") (pin "2") (pinfunction "P_VCC_2") (pintype "passive"))
      (node (ref "ROLLER") (pin "1") (pinfunction "P_VCC_1") (pintype "passive"))
      (node (ref "ROLLER") (pin "2") (pinfunction "P_VCC_2") (pintype "passive"))
    )
    (net (code "48") (name "/R_CE") (class "Default")
      (node (ref "J5") (pin "8") (pinfunction "RADIO_CE_8") (pintype "passive"))
      (node (ref "STM32F407") (pin "2.6") (pinfunction "PC8_2.6") (pintype "passive"))
    )
    (net (code "49") (name "/R_Kick") (class "Default")
      (node (ref "R47") (pin "2") (pinfunction "2_2") (pintype "passive"))
      (node (ref "STM32F407") (pin "1.30") (pinfunction "PB1_1.30") (pintype "passive"))
    )
    (net (code "50") (name "/R_Miso") (class "Default")
      (node (ref "J5") (pin "3") (pinfunction "RADIO_MISO_3") (pintype "passive"))
      (node (ref "STM32F407") (pin "1.5") (pinfunction "PD14_1.5") (pintype "passive"))
    )
    (net (code "51") (name "/R_Mosi") (class "Default")
      (node (ref "J5") (pin "7") (pinfunction "RADIO_MOSI_7") (pintype "passive"))
      (node (ref "STM32F407") (pin "1.7") (pinfunction "PD12_1.7") (pintype "passive"))
    )
    (net (code "52") (name "/R_SCK") (class "Default")
      (node (ref "J5") (pin "9") (pinfunction "RADIO_SCK_9") (pintype "passive"))
      (node (ref "STM32F407") (pin "1.9") (pinfunction "PD10_1.9") (pintype "passive"))
    )
    (net (code "53") (name "/R_SS") (class "Default")
      (node (ref "J5") (pin "10") (pinfunction "RADIO_SS_10") (pintype "passive"))
      (node (ref "STM32F407") (pin "1.11") (pinfunction "PD8_1.11") (pintype "passive"))
    )
    (net (code "54") (name "/SP_M1") (class "Default")
      (node (ref "R21") (pin "1") (pinfunction "1_1") (pintype "passive"))
      (node (ref "STM32F407") (pin "2.13") (pinfunction "PC11_2.13") (pintype "passive"))
    )
    (net (code "55") (name "/SP_M2") (class "Default")
      (node (ref "R31") (pin "1") (pinfunction "1_1") (pintype "passive"))
      (node (ref "STM32F407") (pin "2.39") (pinfunction "PC13_2.39") (pintype "passive"))
    )
    (net (code "56") (name "/SP_M3") (class "Default")
      (node (ref "R32") (pin "1") (pinfunction "1_1") (pintype "passive"))
      (node (ref "STM32F407") (pin "1.40") (pinfunction "PA1_1.40") (pintype "passive"))
    )
    (net (code "57") (name "/SP_M4") (class "Default")
      (node (ref "R22") (pin "1") (pinfunction "1_1") (pintype "passive"))
      (node (ref "STM32F407") (pin "1.18") (pinfunction "PE15_1.18") (pintype "passive"))
    )
    (net (code "58") (name "/SP_MR") (class "Default")
      (node (ref "R11") (pin "1") (pinfunction "1_1") (pintype "passive"))
      (node (ref "STM32F407") (pin "1.6") (pinfunction "PD13_1.6") (pintype "passive"))
    )
    (net (code "59") (name "/Sensor_Bola") (class "Default")
      (node (ref "Q1") (pin "3") (pinfunction "C_3") (pintype "passive"))
      (node (ref "R3") (pin "2") (pinfunction "2_2") (pintype "passive"))
      (node (ref "STM32F407") (pin "1.4") (pinfunction "PD15_1.4") (pintype "passive"))
    )
    (net (code "60") (name "/Shoot_EN") (class "Default")
      (node (ref "Q2") (pin "2") (pinfunction "E_2") (pintype "passive"))
      (node (ref "Q3") (pin "2") (pinfunction "E_2") (pintype "passive"))
      (node (ref "Q4") (pin "2") (pinfunction "E_2") (pintype "passive"))
      (node (ref "STM32F407") (pin "1.26") (pinfunction "PE7_1.26") (pintype "passive"))
    )
    (net (code "61") (name "/~{FAULT}") (class "Default")
      (node (ref "IC3") (pin "9") (pinfunction "S3B_9") (pintype "passive"))
      (node (ref "R52") (pin "2") (pinfunction "2_2") (pintype "passive"))
    )
    (net (code "62") (name "GND") (class "Default")
      (node (ref "C1") (pin "2") (pinfunction "-_2") (pintype "passive"))
      (node (ref "C2") (pin "2") (pinfunction "-_2") (pintype "passive"))
      (node (ref "C3") (pin "2") (pinfunction "2_2") (pintype "passive"))
      (node (ref "C4") (pin "1") (pinfunction "1_1") (pintype "passive"))
      (node (ref "C5") (pin "2") (pinfunction "2_2") (pintype "passive"))
      (node (ref "D1") (pin "2") (pinfunction "A_2") (pintype "passive"))
      (node (ref "D2") (pin "2") (pinfunction "A_2") (pintype "passive"))
      (node (ref "IC2") (pin "4") (pinfunction "GND_4") (pintype "power_in"))
      (node (ref "IC3") (pin "12") (pinfunction "GND_12") (pintype "passive"))
      (node (ref "IC3") (pin "27") (pinfunction "V-_27") (pintype "passive"))
      (node (ref "J10") (pin "2") (pinfunction "GND_2") (pintype "passive"))
      (node (ref "J11") (pin "2") (pinfunction "GND_2") (pintype "passive"))
      (node (ref "J12") (pin "2") (pinfunction "GND_2") (pintype "passive"))
      (node (ref "J13") (pin "2") (pinfunction "GND_2") (pintype "passive"))
      (node (ref "J2") (pin "3") (pinfunction "GROUND_3") (pintype "passive"))
      (node (ref "J2") (pin "5") (pinfunction "~{ON}/OFF_5") (pintype "passive"))
      (node (ref "J2") (pin "6") (pinfunction "GND_6") (pintype "passive"))
      (node (ref "J3") (pin "1") (pinfunction "GND_1") (pintype "power_in"))
      (node (ref "J5") (pin "1") (pinfunction "GND_1") (pintype "passive"))
      (node (ref "J7") (pin "1") (pinfunction "Neg_Led_1") (pintype "passive"))
      (node (ref "J8") (pin "1") (pinfunction "P_GND_1") (pintype "passive"))
      (node (ref "Kick Board") (pin "3") (pinfunction "GND_3") (pintype "passive"))
      (node (ref "Kick Board") (pin "5") (pinfunction "GND_5") (pintype "passive"))
      (node (ref "Kick Board") (pin "7") (pinfunction "GND_7") (pintype "passive"))
      (node (ref "MOTOR1") (pin "10") (pinfunction "GND_10") (pintype "passive"))
      (node (ref "MOTOR1") (pin "9") (pinfunction "P_GND_9") (pintype "passive"))
      (node (ref "MOTOR2") (pin "10") (pinfunction "GND_10") (pintype "passive"))
      (node (ref "MOTOR2") (pin "9") (pinfunction "P_GND_9") (pintype "passive"))
      (node (ref "MOTOR3") (pin "10") (pinfunction "GND_10") (pintype "passive"))
      (node (ref "MOTOR3") (pin "9") (pinfunction "P_GND_9") (pintype "passive"))
      (node (ref "MOTOR4") (pin "10") (pinfunction "GND_10") (pintype "passive"))
      (node (ref "MOTOR4") (pin "9") (pinfunction "P_GND_9") (pintype "passive"))
      (node (ref "Q1") (pin "2") (pinfunction "E_2") (pintype "passive"))
      (node (ref "R2") (pin "1") (pinfunction "1_1") (pintype "passive"))
      (node (ref "R40") (pin "1") (pinfunction "1_1") (pintype "passive"))
      (node (ref "ROLLER") (pin "10") (pinfunction "GND_10") (pintype "passive"))
      (node (ref "ROLLER") (pin "9") (pinfunction "P_GND_9") (pintype "passive"))
      (node (ref "S1") (pin "1") (pinfunction "1_1") (pintype "passive"))
      (node (ref "S1") (pin "2") (pinfunction "2_2") (pintype "passive"))
      (node (ref "S1") (pin "3") (pinfunction "3_3") (pintype "passive"))
      (node (ref "S1") (pin "4") (pinfunction "4_4") (pintype "passive"))
      (node (ref "S1") (pin "5") (pinfunction "5_5") (pintype "passive"))
      (node (ref "STM32F407") (pin "1.1") (pinfunction "GND_1.1") (pintype "passive"))
      (node (ref "STM32F407") (pin "1.2") (pinfunction "GND_1.2") (pintype "passive"))
      (node (ref "STM32F407") (pin "1.28") (pinfunction "GND_1.28") (pintype "passive"))
      (node (ref "STM32F407") (pin "1.46") (pinfunction "GND_1.46") (pintype "passive"))
      (node (ref "STM32F407") (pin "1.49") (pinfunction "GND_1.49") (pintype "passive"))
      (node (ref "STM32F407") (pin "1.50") (pinfunction "GND_1.50") (pintype "passive"))
      (node (ref "STM32F407") (pin "2.1") (pinfunction "GND_2.1") (pintype "passive"))
      (node (ref "STM32F407") (pin "2.2") (pinfunction "GND_2.2") (pintype "passive"))
      (node (ref "STM32F407") (pin "2.49") (pinfunction "GND_2.49") (pintype "passive"))
      (node (ref "STM32F407") (pin "2.50") (pinfunction "GND_2.50") (pintype "passive"))
    )
    (net (code "63") (name "Net-(C5-Pad1)") (class "Default")
      (node (ref "C5") (pin "1") (pinfunction "1_1") (pintype "passive"))
      (node (ref "R38") (pin "1") (pinfunction "1_1") (pintype "passive"))
      (node (ref "R39") (pin "2") (pinfunction "2_2") (pintype "passive"))
    )
    (net (code "64") (name "Net-(D1-K)") (class "Default")
      (node (ref "D1") (pin "1") (pinfunction "K_1") (pintype "passive"))
      (node (ref "J2") (pin "2") (pinfunction "OUTPUT_2") (pintype "passive"))
      (node (ref "L1") (pin "1") (pinfunction "1_1") (pintype "passive"))
    )
    (net (code "65") (name "Net-(IC2-IN1+)") (class "Default")
      (node (ref "IC2") (pin "3") (pinfunction "IN1+_3") (pintype "input"))
      (node (ref "R39") (pin "1") (pinfunction "1_1") (pintype "passive"))
    )
    (net (code "66") (name "Net-(J1-Out)") (class "Default")
      (node (ref "J1") (pin "2") (pinfunction "Out_2") (pintype "passive"))
      (node (ref "J4") (pin "1") (pinfunction "1_1") (pintype "passive"))
    )
    (net (code "67") (name "Net-(J2-FEED_BACK)") (class "Default")
      (node (ref "J2") (pin "4") (pinfunction "FEED_BACK_4") (pintype "passive"))
      (node (ref "R1") (pin "1") (pinfunction "1_1") (pintype "passive"))
      (node (ref "R2") (pin "2") (pinfunction "2_2") (pintype "passive"))
    )
    (net (code "68") (name "Net-(J6-Sensor)") (class "Default")
      (node (ref "J6") (pin "3") (pinfunction "Sensor_3") (pintype "passive"))
      (node (ref "R4") (pin "2") (pinfunction "2_2") (pintype "passive"))
      (node (ref "R5") (pin "2") (pinfunction "2_2") (pintype "passive"))
    )
    (net (code "69") (name "Net-(J7-Pos_Led)") (class "Default")
      (node (ref "J7") (pin "2") (pinfunction "Pos_Led_2") (pintype "passive"))
      (node (ref "R6") (pin "1") (pinfunction "1_1") (pintype "passive"))
    )
    (net (code "70") (name "Net-(J10-Ch_A)") (class "Default")
      (node (ref "J10") (pin "1") (pinfunction "Ch_A_1") (pintype "passive"))
      (node (ref "R43") (pin "2") (pinfunction "2_2") (pintype "passive"))
    )
    (net (code "71") (name "Net-(J10-Ch_B)") (class "Default")
      (node (ref "J10") (pin "3") (pinfunction "Ch_B_3") (pintype "passive"))
      (node (ref "R41") (pin "2") (pinfunction "2_2") (pintype "passive"))
    )
    (net (code "72") (name "Net-(J11-Ch_A)") (class "Default")
      (node (ref "J11") (pin "1") (pinfunction "Ch_A_1") (pintype "passive"))
      (node (ref "R42") (pin "1") (pinfunction "1_1") (pintype "passive"))
    )
    (net (code "73") (name "Net-(J11-Ch_B)") (class "Default")
      (node (ref "J11") (pin "3") (pinfunction "Ch_B_3") (pintype "passive"))
      (node (ref "R44") (pin "1") (pinfunction "1_1") (pintype "passive"))
    )
    (net (code "74") (name "Net-(J12-Ch_A)") (class "Default")
      (node (ref "J12") (pin "1") (pinfunction "Ch_A_1") (pintype "passive"))
      (node (ref "R49") (pin "2") (pinfunction "2_2") (pintype "passive"))
    )
    (net (code "75") (name "Net-(J12-Ch_B)") (class "Default")
      (node (ref "J12") (pin "3") (pinfunction "Ch_B_3") (pintype "passive"))
      (node (ref "R48") (pin "2") (pinfunction "2_2") (pintype "passive"))
    )
    (net (code "76") (name "Net-(J13-Ch_A)") (class "Default")
      (node (ref "J13") (pin "1") (pinfunction "Ch_A_1") (pintype "passive"))
      (node (ref "R50") (pin "1") (pinfunction "1_1") (pintype "passive"))
    )
    (net (code "77") (name "Net-(J13-Ch_B)") (class "Default")
      (node (ref "J13") (pin "3") (pinfunction "Ch_B_3") (pintype "passive"))
      (node (ref "R51") (pin "1") (pinfunction "1_1") (pintype "passive"))
    )
    (net (code "78") (name "Net-(Kick Board-Chip_Kick)") (class "Default")
      (node (ref "Kick Board") (pin "1") (pinfunction "Chip_Kick_1") (pintype "passive"))
      (node (ref "Q2") (pin "3") (pinfunction "C_3") (pintype "passive"))
    )
    (net (code "79") (name "Net-(Kick Board-L_Kick)") (class "Default")
      (node (ref "Kick Board") (pin "6") (pinfunction "L_Kick_6") (pintype "passive"))
      (node (ref "Q3") (pin "3") (pinfunction "C_3") (pintype "passive"))
    )
    (net (code "80") (name "Net-(Kick Board-R_Kick)") (class "Default")
      (node (ref "Kick Board") (pin "4") (pinfunction "R_Kick_4") (pintype "passive"))
      (node (ref "Q4") (pin "3") (pinfunction "C_3") (pintype "passive"))
    )
    (net (code "81") (name "Net-(Kick Board-~{FAULT})") (class "Default")
      (node (ref "Kick Board") (pin "8") (pinfunction "~{FAULT}_8") (pintype "passive"))
      (node (ref "R52") (pin "1") (pinfunction "1_1") (pintype "passive"))
    )
    (net (code "82") (name "Net-(MOTOR1-BRAKE)") (class "Default")
      (node (ref "MOTOR1") (pin "7") (pinfunction "BRAKE_7") (pintype "passive"))
      (node (ref "R20") (pin "2") (pinfunction "2_2") (pintype "passive"))
    )
    (net (code "83") (name "Net-(MOTOR1-DIR)") (class "Default")
      (node (ref "MOTOR1") (pin "5") (pinfunction "DIR_5") (pintype "passive"))
      (node (ref "R19") (pin "2") (pinfunction "2_2") (pintype "passive"))
    )
    (net (code "84") (name "Net-(MOTOR1-ENABLE)") (class "Default")
      (node (ref "MOTOR1") (pin "3") (pinfunction "ENABLE_3") (pintype "passive"))
      (node (ref "R17") (pin "2") (pinfunction "2_2") (pintype "passive"))
    )
    (net (code "85") (name "Net-(MOTOR1-FAULT)") (class "Default")
      (node (ref "MOTOR1") (pin "4") (pinfunction "FAULT_4") (pintype "passive"))
      (node (ref "R18") (pin "2") (pinfunction "2_2") (pintype "passive"))
    )
    (net (code "86") (name "Net-(MOTOR1-SPEED)") (class "Default")
      (node (ref "MOTOR1") (pin "8") (pinfunction "SPEED_8") (pintype "passive"))
      (node (ref "R21") (pin "2") (pinfunction "2_2") (pintype "passive"))
    )
    (net (code "87") (name "Net-(MOTOR2-BRAKE)") (class "Default")
      (node (ref "MOTOR2") (pin "7") (pinfunction "BRAKE_7") (pintype "passive"))
      (node (ref "R30") (pin "2") (pinfunction "2_2") (pintype "passive"))
    )
    (net (code "88") (name "Net-(MOTOR2-DIR)") (class "Default")
      (node (ref "MOTOR2") (pin "5") (pinfunction "DIR_5") (pintype "passive"))
      (node (ref "R29") (pin "2") (pinfunction "2_2") (pintype "passive"))
    )
    (net (code "89") (name "Net-(MOTOR2-ENABLE)") (class "Default")
      (node (ref "MOTOR2") (pin "3") (pinfunction "ENABLE_3") (pintype "passive"))
      (node (ref "R27") (pin "2") (pinfunction "2_2") (pintype "passive"))
    )
    (net (code "90") (name "Net-(MOTOR2-FAULT)") (class "Default")
      (node (ref "MOTOR2") (pin "4") (pinfunction "FAULT_4") (pintype "passive"))
      (node (ref "R28") (pin "2") (pinfunction "2_2") (pintype "passive"))
    )
    (net (code "91") (name "Net-(MOTOR2-SPEED)") (class "Default")
      (node (ref "MOTOR2") (pin "8") (pinfunction "SPEED_8") (pintype "passive"))
      (node (ref "R31") (pin "2") (pinfunction "2_2") (pintype "passive"))
    )
    (net (code "92") (name "Net-(MOTOR3-BRAKE)") (class "Default")
      (node (ref "MOTOR3") (pin "7") (pinfunction "BRAKE_7") (pintype "passive"))
      (node (ref "R33") (pin "2") (pinfunction "2_2") (pintype "passive"))
    )
    (net (code "93") (name "Net-(MOTOR3-DIR)") (class "Default")
      (node (ref "MOTOR3") (pin "5") (pinfunction "DIR_5") (pintype "passive"))
      (node (ref "R34") (pin "2") (pinfunction "2_2") (pintype "passive"))
    )
    (net (code "94") (name "Net-(MOTOR3-ENABLE)") (class "Default")
      (node (ref "MOTOR3") (pin "3") (pinfunction "ENABLE_3") (pintype "passive"))
      (node (ref "R36") (pin "2") (pinfunction "2_2") (pintype "passive"))
    )
    (net (code "95") (name "Net-(MOTOR3-FAULT)") (class "Default")
      (node (ref "MOTOR3") (pin "4") (pinfunction "FAULT_4") (pintype "passive"))
      (node (ref "R35") (pin "2") (pinfunction "2_2") (pintype "passive"))
    )
    (net (code "96") (name "Net-(MOTOR3-SPEED)") (class "Default")
      (node (ref "MOTOR3") (pin "8") (pinfunction "SPEED_8") (pintype "passive"))
      (node (ref "R32") (pin "2") (pinfunction "2_2") (pintype "passive"))
    )
    (net (code "97") (name "Net-(MOTOR4-BRAKE)") (class "Default")
      (node (ref "MOTOR4") (pin "7") (pinfunction "BRAKE_7") (pintype "passive"))
      (node (ref "R23") (pin "2") (pinfunction "2_2") (pintype "passive"))
    )
    (net (code "98") (name "Net-(MOTOR4-DIR)") (class "Default")
      (node (ref "MOTOR4") (pin "5") (pinfunction "DIR_5") (pintype "passive"))
      (node (ref "R24") (pin "2") (pinfunction "2_2") (pintype "passive"))
    )
    (net (code "99") (name "Net-(MOTOR4-ENABLE)") (class "Default")
      (node (ref "MOTOR4") (pin "3") (pinfunction "ENABLE_3") (pintype "passive"))
      (node (ref "R26") (pin "2") (pinfunction "2_2") (pintype "passive"))
    )
    (net (code "100") (name "Net-(MOTOR4-FAULT)") (class "Default")
      (node (ref "MOTOR4") (pin "4") (pinfunction "FAULT_4") (pintype "passive"))
      (node (ref "R25") (pin "2") (pinfunction "2_2") (pintype "passive"))
    )
    (net (code "101") (name "Net-(MOTOR4-SPEED)") (class "Default")
      (node (ref "MOTOR4") (pin "8") (pinfunction "SPEED_8") (pintype "passive"))
      (node (ref "R22") (pin "2") (pinfunction "2_2") (pintype "passive"))
    )
    (net (code "102") (name "Net-(Q1-B)") (class "Default")
      (node (ref "Q1") (pin "1") (pinfunction "B_1") (pintype "passive"))
      (node (ref "R5") (pin "1") (pinfunction "1_1") (pintype "passive"))
    )
    (net (code "103") (name "Net-(Q2-B)") (class "Default")
      (node (ref "Q2") (pin "1") (pinfunction "B_1") (pintype "passive"))
      (node (ref "R45") (pin "1") (pinfunction "1_1") (pintype "passive"))
    )
    (net (code "104") (name "Net-(Q3-B)") (class "Default")
      (node (ref "Q3") (pin "1") (pinfunction "B_1") (pintype "passive"))
      (node (ref "R46") (pin "1") (pinfunction "1_1") (pintype "passive"))
    )
    (net (code "105") (name "Net-(Q4-B)") (class "Default")
      (node (ref "Q4") (pin "1") (pinfunction "B_1") (pintype "passive"))
      (node (ref "R47") (pin "1") (pinfunction "1_1") (pintype "passive"))
    )
    (net (code "106") (name "Net-(R37-Pad1)") (class "Default")
      (node (ref "R37") (pin "1") (pinfunction "1_1") (pintype "passive"))
      (node (ref "R38") (pin "2") (pinfunction "2_2") (pintype "passive"))
      (node (ref "R40") (pin "2") (pinfunction "2_2") (pintype "passive"))
    )
    (net (code "107") (name "Net-(ROLLER-BRAKE)") (class "Default")
      (node (ref "R10") (pin "2") (pinfunction "2_2") (pintype "passive"))
      (node (ref "ROLLER") (pin "7") (pinfunction "BRAKE_7") (pintype "passive"))
    )
    (net (code "108") (name "Net-(ROLLER-DIR)") (class "Default")
      (node (ref "R9") (pin "2") (pinfunction "2_2") (pintype "passive"))
      (node (ref "ROLLER") (pin "5") (pinfunction "DIR_5") (pintype "passive"))
    )
    (net (code "109") (name "Net-(ROLLER-ENABLE)") (class "Default")
      (node (ref "R7") (pin "2") (pinfunction "2_2") (pintype "passive"))
      (node (ref "ROLLER") (pin "3") (pinfunction "ENABLE_3") (pintype "passive"))
    )
    (net (code "110") (name "Net-(ROLLER-FAULT)") (class "Default")
      (node (ref "R8") (pin "2") (pinfunction "2_2") (pintype "passive"))
      (node (ref "ROLLER") (pin "4") (pinfunction "FAULT_4") (pintype "passive"))
    )
    (net (code "111") (name "Net-(ROLLER-SPEED)") (class "Default")
      (node (ref "R11") (pin "2") (pinfunction "2_2") (pintype "passive"))
      (node (ref "ROLLER") (pin "8") (pinfunction "SPEED_8") (pintype "passive"))
    )
    (net (code "112") (name "unconnected-(IC2-IN2+-Pad5)") (class "Default")
      (node (ref "IC2") (pin "5") (pinfunction "IN2+_5") (pintype "input"))
    )
    (net (code "113") (name "unconnected-(IC2-IN2--Pad6)") (class "Default")
      (node (ref "IC2") (pin "6") (pinfunction "IN2-_6") (pintype "input"))
    )
    (net (code "114") (name "unconnected-(IC2-OUT2-Pad7)") (class "Default")
      (node (ref "IC2") (pin "7") (pinfunction "OUT2_7") (pintype "output"))
    )
    (net (code "115") (name "unconnected-(IC3-NC-Pad14)") (class "Default")
      (node (ref "IC3") (pin "14") (pinfunction "NC_14") (pintype "passive"))
    )
    (net (code "116") (name "unconnected-(IC3-NC_2-Pad3)") (class "Default")
      (node (ref "IC3") (pin "3") (pinfunction "NC_2_3") (pintype "passive"))
    )
    (net (code "117") (name "unconnected-(IC3-NC_3-Pad13)") (class "Default")
      (node (ref "IC3") (pin "13") (pinfunction "NC_3_13") (pintype "passive"))
    )
    (net (code "118") (name "unconnected-(IC3-S6A-Pad24)") (class "Default")
      (node (ref "IC3") (pin "24") (pinfunction "S6A_24") (pintype "passive"))
    )
    (net (code "119") (name "unconnected-(IC3-S7A-Pad25)") (class "Default")
      (node (ref "IC3") (pin "25") (pinfunction "S7A_25") (pintype "passive"))
    )
    (net (code "120") (name "unconnected-(IC3-S8A-Pad26)") (class "Default")
      (node (ref "IC3") (pin "26") (pinfunction "S8A_26") (pintype "passive"))
    )
    (net (code "121") (name "unconnected-(IC3-S8B-Pad4)") (class "Default")
      (node (ref "IC3") (pin "4") (pinfunction "S8B_4") (pintype "passive"))
    )
    (net (code "122") (name "unconnected-(J5-NC-Pad4)") (class "Default")
      (node (ref "J5") (pin "4") (pinfunction "NC_4") (pintype "passive"))
    )
    (net (code "123") (name "unconnected-(J5-NC-Pad5)") (class "Default")
      (node (ref "J5") (pin "5") (pinfunction "NC_5") (pintype "passive"))
    )
    (net (code "124") (name "unconnected-(J5-NC-Pad6)") (class "Default")
      (node (ref "J5") (pin "6") (pinfunction "NC_6") (pintype "passive"))
    )
    (net (code "125") (name "unconnected-(J6-NC-Pad1)") (class "Default")
      (node (ref "J6") (pin "1") (pinfunction "NC_1") (pintype "passive"))
    )
    (net (code "126") (name "unconnected-(STM32F407-BOOT0-Pad2.30)") (class "Default")
      (node (ref "STM32F407") (pin "2.30") (pinfunction "BOOT0_2.30") (pintype "passive"))
    )
    (net (code "127") (name "unconnected-(STM32F407-NC-Pad1.3)") (class "Default")
      (node (ref "STM32F407") (pin "1.3") (pinfunction "NC_1.3") (pintype "passive"))
    )
    (net (code "128") (name "unconnected-(STM32F407-NRST-Pad1.45)") (class "Default")
      (node (ref "STM32F407") (pin "1.45") (pinfunction "NRST_1.45") (pintype "passive"))
    )
    (net (code "129") (name "unconnected-(STM32F407-PA0-Pad1.39)") (class "Default")
      (node (ref "STM32F407") (pin "1.39") (pinfunction "PA0_1.39") (pintype "passive"))
    )
    (net (code "130") (name "unconnected-(STM32F407-PA2-Pad1.37)") (class "Default")
      (node (ref "STM32F407") (pin "1.37") (pinfunction "PA2_1.37") (pintype "passive"))
    )
    (net (code "131") (name "unconnected-(STM32F407-PA5-Pad1.36)") (class "Default")
      (node (ref "STM32F407") (pin "1.36") (pinfunction "PA5_1.36") (pintype "passive"))
    )
    (net (code "132") (name "unconnected-(STM32F407-PA7-Pad1.34)") (class "Default")
      (node (ref "STM32F407") (pin "1.34") (pinfunction "PA7_1.34") (pintype "passive"))
    )
    (net (code "133") (name "unconnected-(STM32F407-PA8-Pad2.8)") (class "Default")
      (node (ref "STM32F407") (pin "2.8") (pinfunction "PA8_2.8") (pintype "passive"))
    )
    (net (code "134") (name "unconnected-(STM32F407-PA9-Pad2.7)") (class "Default")
      (node (ref "STM32F407") (pin "2.7") (pinfunction "PA9_2.7") (pintype "passive"))
    )
    (net (code "135") (name "unconnected-(STM32F407-PA10-Pad2.10)") (class "Default")
      (node (ref "STM32F407") (pin "2.10") (pinfunction "PA10_2.10") (pintype "passive"))
    )
    (net (code "136") (name "unconnected-(STM32F407-PA13-Pad2.9)") (class "Default")
      (node (ref "STM32F407") (pin "2.9") (pinfunction "PA13_2.9") (pintype "passive"))
    )
    (net (code "137") (name "unconnected-(STM32F407-PA14-Pad2.12)") (class "Default")
      (node (ref "STM32F407") (pin "2.12") (pinfunction "PA14_2.12") (pintype "passive"))
    )
    (net (code "138") (name "unconnected-(STM32F407-PA15-Pad2.11)") (class "Default")
      (node (ref "STM32F407") (pin "2.11") (pinfunction "PA15_2.11") (pintype "passive"))
    )
    (net (code "139") (name "unconnected-(STM32F407-PB0-Pad1.29)") (class "Default")
      (node (ref "STM32F407") (pin "1.29") (pinfunction "PB0_1.29") (pintype "passive"))
    )
    (net (code "140") (name "unconnected-(STM32F407-PB2-Pad1.27)") (class "Default")
      (node (ref "STM32F407") (pin "1.27") (pinfunction "PB2_1.27") (pintype "passive"))
    )
    (net (code "141") (name "unconnected-(STM32F407-PB3-Pad2.23)") (class "Default")
      (node (ref "STM32F407") (pin "2.23") (pinfunction "PB3_2.23") (pintype "passive"))
    )
    (net (code "142") (name "unconnected-(STM32F407-PB4-Pad2.26)") (class "Default")
      (node (ref "STM32F407") (pin "2.26") (pinfunction "PB4_2.26") (pintype "passive"))
    )
    (net (code "143") (name "unconnected-(STM32F407-PB5-Pad2.25)") (class "Default")
      (node (ref "STM32F407") (pin "2.25") (pinfunction "PB5_2.25") (pintype "passive"))
    )
    (net (code "144") (name "unconnected-(STM32F407-PB6-Pad2.28)") (class "Default")
      (node (ref "STM32F407") (pin "2.28") (pinfunction "PB6_2.28") (pintype "passive"))
    )
    (net (code "145") (name "unconnected-(STM32F407-PB7-Pad2.27)") (class "Default")
      (node (ref "STM32F407") (pin "2.27") (pinfunction "PB7_2.27") (pintype "passive"))
    )
    (net (code "146") (name "unconnected-(STM32F407-PB8-Pad2.32)") (class "Default")
      (node (ref "STM32F407") (pin "2.32") (pinfunction "PB8_2.32") (pintype "passive"))
    )
    (net (code "147") (name "unconnected-(STM32F407-PB9-Pad2.31)") (class "Default")
      (node (ref "STM32F407") (pin "2.31") (pinfunction "PB9_2.31") (pintype "passive"))
    )
    (net (code "148") (name "unconnected-(STM32F407-PB10-Pad1.17)") (class "Default")
      (node (ref "STM32F407") (pin "1.17") (pinfunction "PB10_1.17") (pintype "passive"))
    )
    (net (code "149") (name "unconnected-(STM32F407-PB11-Pad1.16)") (class "Default")
      (node (ref "STM32F407") (pin "1.16") (pinfunction "PB11_1.16") (pintype "passive"))
    )
    (net (code "150") (name "unconnected-(STM32F407-PB12-Pad1.15)") (class "Default")
      (node (ref "STM32F407") (pin "1.15") (pinfunction "PB12_1.15") (pintype "passive"))
    )
    (net (code "151") (name "unconnected-(STM32F407-PB13-Pad1.14)") (class "Default")
      (node (ref "STM32F407") (pin "1.14") (pinfunction "PB13_1.14") (pintype "passive"))
    )
    (net (code "152") (name "unconnected-(STM32F407-PB14-Pad1.13)") (class "Default")
      (node (ref "STM32F407") (pin "1.13") (pinfunction "PB14_1.13") (pintype "passive"))
    )
    (net (code "153") (name "unconnected-(STM32F407-PC0-Pad1.43)") (class "Default")
      (node (ref "STM32F407") (pin "1.43") (pinfunction "PC0_1.43") (pintype "passive"))
    )
    (net (code "154") (name "unconnected-(STM32F407-PC3-Pad1.42)") (class "Default")
      (node (ref "STM32F407") (pin "1.42") (pinfunction "PC3_1.42") (pintype "passive"))
    )
    (net (code "155") (name "unconnected-(STM32F407-PC4-Pad1.31)") (class "Default")
      (node (ref "STM32F407") (pin "1.31") (pinfunction "PC4_1.31") (pintype "passive"))
    )
    (net (code "156") (name "unconnected-(STM32F407-PC7-Pad2.3)") (class "Default")
      (node (ref "STM32F407") (pin "2.3") (pinfunction "PC7_2.3") (pintype "passive"))
    )
    (net (code "157") (name "unconnected-(STM32F407-PC10-Pad2.14)") (class "Default")
      (node (ref "STM32F407") (pin "2.14") (pinfunction "PC10_2.14") (pintype "passive"))
    )
    (net (code "158") (name "unconnected-(STM32F407-PD1-Pad2.18)") (class "Default")
      (node (ref "STM32F407") (pin "2.18") (pinfunction "PD1_2.18") (pintype "passive"))
    )
    (net (code "159") (name "unconnected-(STM32F407-PD2-Pad2.17)") (class "Default")
      (node (ref "STM32F407") (pin "2.17") (pinfunction "PD2_2.17") (pintype "passive"))
    )
    (net (code "160") (name "unconnected-(STM32F407-PD4-Pad2.19)") (class "Default")
      (node (ref "STM32F407") (pin "2.19") (pinfunction "PD4_2.19") (pintype "passive"))
    )
    (net (code "161") (name "unconnected-(STM32F407-PD5-Pad2.22)") (class "Default")
      (node (ref "STM32F407") (pin "2.22") (pinfunction "PD5_2.22") (pintype "passive"))
    )
    (net (code "162") (name "unconnected-(STM32F407-PD12-Pad2.16)") (class "Default")
      (node (ref "STM32F407") (pin "2.16") (pinfunction "PD12_2.16") (pintype "passive"))
    )
    (net (code "163") (name "unconnected-(STM32F407-PE0-Pad2.34)") (class "Default")
      (node (ref "STM32F407") (pin "2.34") (pinfunction "PE0_2.34") (pintype "passive"))
    )
    (net (code "164") (name "unconnected-(STM32F407-PE1-Pad2.33)") (class "Default")
      (node (ref "STM32F407") (pin "2.33") (pinfunction "PE1_2.33") (pintype "passive"))
    )
    (net (code "165") (name "unconnected-(STM32F407-PE3-Pad2.35)") (class "Default")
      (node (ref "STM32F407") (pin "2.35") (pinfunction "PE3_2.35") (pintype "passive"))
    )
  )
)
